# 7seg_clock_ver2.net
KiCad netlist of a schematic drawn in EAGLE
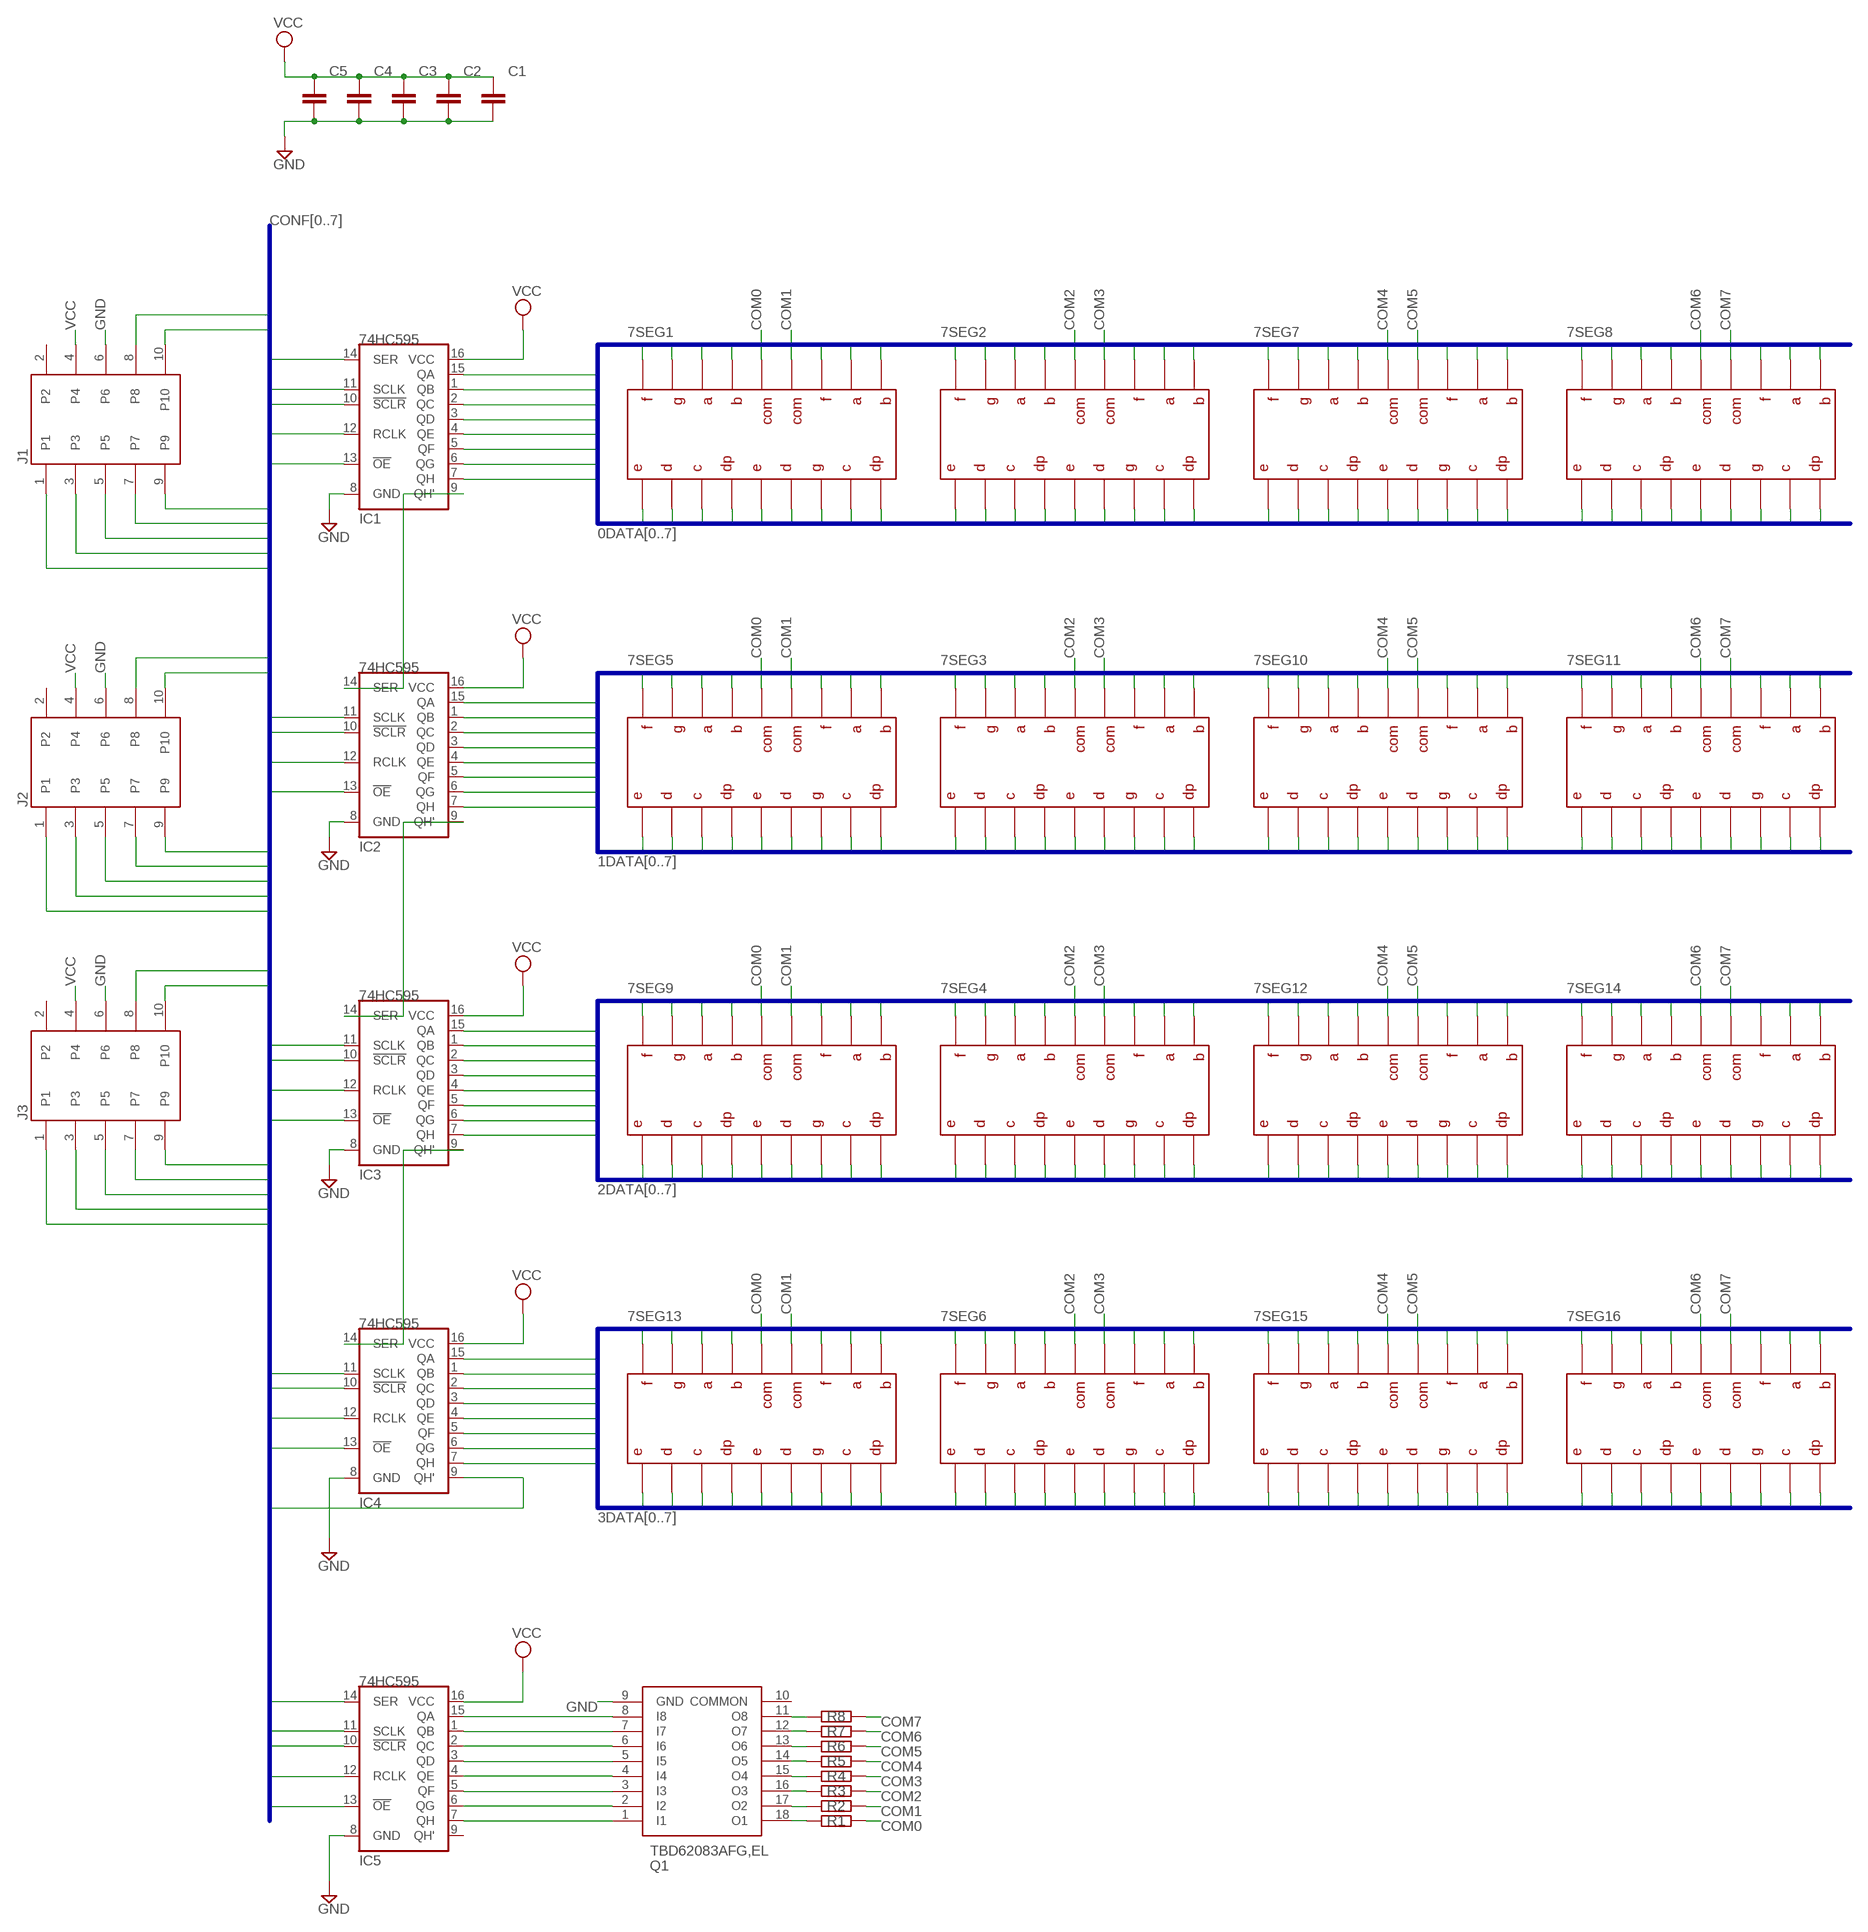
[diagram p0: schematic, sheet 1]

(export (version "E")
  (design (tool "Eeschema 10.0.6"))
  (components
    (comp (ref "7SEG1")
      (value "SL-3264")
      (footprint "eagle-import:SL-3264")
      (libsource (lib "eagle-import") (part "SL-3264"))
    )
    (comp (ref "7SEG2")
      (value "SL-3264")
      (footprint "eagle-import:SL-3264")
      (libsource (lib "eagle-import") (part "SL-3264"))
    )
    (comp (ref "7SEG3")
      (value "SL-3264")
      (footprint "eagle-import:SL-3264")
      (libsource (lib "eagle-import") (part "SL-3264"))
    )
    (comp (ref "7SEG4")
      (value "SL-3264")
      (footprint "eagle-import:SL-3264")
      (libsource (lib "eagle-import") (part "SL-3264"))
    )
    (comp (ref "7SEG5")
      (value "SL-3264")
      (footprint "eagle-import:SL-3264")
      (libsource (lib "eagle-import") (part "SL-3264"))
    )
    (comp (ref "7SEG6")
      (value "SL-3264")
      (footprint "eagle-import:SL-3264")
      (libsource (lib "eagle-import") (part "SL-3264"))
    )
    (comp (ref "7SEG7")
      (value "SL-3264")
      (footprint "eagle-import:SL-3264")
      (libsource (lib "eagle-import") (part "SL-3264"))
    )
    (comp (ref "7SEG8")
      (value "SL-3264")
      (footprint "eagle-import:SL-3264")
      (libsource (lib "eagle-import") (part "SL-3264"))
    )
    (comp (ref "7SEG9")
      (value "SL-3264")
      (footprint "eagle-import:SL-3264")
      (libsource (lib "eagle-import") (part "SL-3264"))
    )
    (comp (ref "7SEG10")
      (value "SL-3264")
      (footprint "eagle-import:SL-3264")
      (libsource (lib "eagle-import") (part "SL-3264"))
    )
    (comp (ref "7SEG11")
      (value "SL-3264")
      (footprint "eagle-import:SL-3264")
      (libsource (lib "eagle-import") (part "SL-3264"))
    )
    (comp (ref "7SEG12")
      (value "SL-3264")
      (footprint "eagle-import:SL-3264")
      (libsource (lib "eagle-import") (part "SL-3264"))
    )
    (comp (ref "7SEG13")
      (value "SL-3264")
      (footprint "eagle-import:SL-3264")
      (libsource (lib "eagle-import") (part "SL-3264"))
    )
    (comp (ref "7SEG14")
      (value "SL-3264")
      (footprint "eagle-import:SL-3264")
      (libsource (lib "eagle-import") (part "SL-3264"))
    )
    (comp (ref "7SEG15")
      (value "SL-3264")
      (footprint "eagle-import:SL-3264")
      (libsource (lib "eagle-import") (part "SL-3264"))
    )
    (comp (ref "7SEG16")
      (value "SL-3264")
      (footprint "eagle-import:SL-3264")
      (libsource (lib "eagle-import") (part "SL-3264"))
    )
    (comp (ref "C1")
      (value "C_CHIP-0603(1608-METRIC)")
      (footprint "eagle-import:CAPC1608X85")
      (libsource (lib "eagle-import") (part "CCHIP-0603(1608-METRIC)_"))
    )
    (comp (ref "C2")
      (value "C_CHIP-0603(1608-METRIC)")
      (footprint "eagle-import:CAPC1608X85")
      (libsource (lib "eagle-import") (part "CCHIP-0603(1608-METRIC)_"))
    )
    (comp (ref "C3")
      (value "C_CHIP-0603(1608-METRIC)")
      (footprint "eagle-import:CAPC1608X85")
      (libsource (lib "eagle-import") (part "CCHIP-0603(1608-METRIC)_"))
    )
    (comp (ref "C4")
      (value "C_CHIP-0603(1608-METRIC)")
      (footprint "eagle-import:CAPC1608X85")
      (libsource (lib "eagle-import") (part "CCHIP-0603(1608-METRIC)_"))
    )
    (comp (ref "C5")
      (value "C_CHIP-0603(1608-METRIC)")
      (footprint "eagle-import:CAPC1608X85")
      (libsource (lib "eagle-import") (part "CCHIP-0603(1608-METRIC)_"))
    )
    (comp (ref "IC1")
      (value "74HC595")
      (footprint "eagle-import:SO16")
      (fields (field (name "MF") "Nexperia"))
      (libsource (lib "eagle-import") (part "74HC595"))
    )
    (comp (ref "IC2")
      (value "74HC595")
      (footprint "eagle-import:SO16")
      (fields (field (name "MF") "Nexperia"))
      (libsource (lib "eagle-import") (part "74HC595"))
    )
    (comp (ref "IC3")
      (value "74HC595")
      (footprint "eagle-import:SO16")
      (fields (field (name "MF") "Nexperia"))
      (libsource (lib "eagle-import") (part "74HC595"))
    )
    (comp (ref "IC4")
      (value "74HC595")
      (footprint "eagle-import:SO16")
      (fields (field (name "MF") "Nexperia"))
      (libsource (lib "eagle-import") (part "74HC595"))
    )
    (comp (ref "IC5")
      (value "74HC595")
      (footprint "eagle-import:SO16")
      (fields (field (name "MF") "Nexperia"))
      (libsource (lib "eagle-import") (part "74HC595"))
    )
    (comp (ref "J1")
      (value "1241050-5")
      (footprint "eagle-import:TE_1241050-5")
      (fields (field (name "MF") "TE Connectivity"))
      (libsource (lib "eagle-import") (part "1241050-5"))
    )
    (comp (ref "J2")
      (value "1241050-5")
      (footprint "eagle-import:TE_1241050-5")
      (fields (field (name "MF") "TE Connectivity"))
      (libsource (lib "eagle-import") (part "1241050-5"))
    )
    (comp (ref "J3")
      (value "1241050-5")
      (footprint "eagle-import:TE_1241050-5")
      (fields (field (name "MF") "TE Connectivity"))
      (libsource (lib "eagle-import") (part "1241050-5"))
    )
    (comp (ref "Q1")
      (value "TBD62083AFG,EL")
      (footprint "eagle-import:SOIC127P1030X245-18N")
      (fields (field (name "MF") "Toshiba Semiconductor"))
      (libsource (lib "eagle-import") (part "TBD62083AFG,EL"))
    )
    (comp (ref "R1")
      (value "R_CHIP-0603(1608-METRIC)")
      (footprint "eagle-import:RESC1608X60")
      (libsource (lib "eagle-import") (part "RCHIP-0603(1608-METRIC)_"))
    )
    (comp (ref "R2")
      (value "R_CHIP-0603(1608-METRIC)")
      (footprint "eagle-import:RESC1608X60")
      (libsource (lib "eagle-import") (part "RCHIP-0603(1608-METRIC)_"))
    )
    (comp (ref "R3")
      (value "R_CHIP-0603(1608-METRIC)")
      (footprint "eagle-import:RESC1608X60")
      (libsource (lib "eagle-import") (part "RCHIP-0603(1608-METRIC)_"))
    )
    (comp (ref "R4")
      (value "R_CHIP-0603(1608-METRIC)")
      (footprint "eagle-import:RESC1608X60")
      (libsource (lib "eagle-import") (part "RCHIP-0603(1608-METRIC)_"))
    )
    (comp (ref "R5")
      (value "R_CHIP-0603(1608-METRIC)")
      (footprint "eagle-import:RESC1608X60")
      (libsource (lib "eagle-import") (part "RCHIP-0603(1608-METRIC)_"))
    )
    (comp (ref "R6")
      (value "R_CHIP-0603(1608-METRIC)")
      (footprint "eagle-import:RESC1608X60")
      (libsource (lib "eagle-import") (part "RCHIP-0603(1608-METRIC)_"))
    )
    (comp (ref "R7")
      (value "R_CHIP-0603(1608-METRIC)")
      (footprint "eagle-import:RESC1608X60")
      (libsource (lib "eagle-import") (part "RCHIP-0603(1608-METRIC)_"))
    )
    (comp (ref "R8")
      (value "R_CHIP-0603(1608-METRIC)")
      (footprint "eagle-import:RESC1608X60")
      (libsource (lib "eagle-import") (part "RCHIP-0603(1608-METRIC)_"))
    )
  )
  (nets
    (net (code "2") (name "/0DATA0") (class "Default")
      (node (ref "7SEG1") (pin "P$10") (pinfunction "P$10_P$10") (pintype "bidirectional"))
      (node (ref "7SEG1") (pin "P$15") (pinfunction "P$15_P$15") (pintype "bidirectional"))
      (node (ref "7SEG2") (pin "P$10") (pinfunction "P$10_P$10") (pintype "bidirectional"))
      (node (ref "7SEG2") (pin "P$15") (pinfunction "P$15_P$15") (pintype "bidirectional"))
      (node (ref "7SEG7") (pin "P$10") (pinfunction "P$10_P$10") (pintype "bidirectional"))
      (node (ref "7SEG7") (pin "P$15") (pinfunction "P$15_P$15") (pintype "bidirectional"))
      (node (ref "7SEG8") (pin "P$10") (pinfunction "P$10_P$10") (pintype "bidirectional"))
      (node (ref "7SEG8") (pin "P$15") (pinfunction "P$15_P$15") (pintype "bidirectional"))
      (node (ref "IC1") (pin "15") (pinfunction "QA_15") (pintype "tri_state"))
    )
    (net (code "3") (name "/0DATA1") (class "Default")
      (node (ref "7SEG1") (pin "P$12") (pinfunction "P$12_P$12") (pintype "bidirectional"))
      (node (ref "7SEG1") (pin "P$18") (pinfunction "P$18_P$18") (pintype "bidirectional"))
      (node (ref "7SEG2") (pin "P$12") (pinfunction "P$12_P$12") (pintype "bidirectional"))
      (node (ref "7SEG2") (pin "P$18") (pinfunction "P$18_P$18") (pintype "bidirectional"))
      (node (ref "7SEG7") (pin "P$12") (pinfunction "P$12_P$12") (pintype "bidirectional"))
      (node (ref "7SEG7") (pin "P$18") (pinfunction "P$18_P$18") (pintype "bidirectional"))
      (node (ref "7SEG8") (pin "P$12") (pinfunction "P$12_P$12") (pintype "bidirectional"))
      (node (ref "7SEG8") (pin "P$18") (pinfunction "P$18_P$18") (pintype "bidirectional"))
      (node (ref "IC1") (pin "1") (pinfunction "QB_1") (pintype "tri_state"))
    )
    (net (code "4") (name "/0DATA2") (class "Default")
      (node (ref "7SEG1") (pin "P$17") (pinfunction "P$17_P$17") (pintype "bidirectional"))
      (node (ref "7SEG1") (pin "P$7") (pinfunction "P$7_P$7") (pintype "bidirectional"))
      (node (ref "7SEG2") (pin "P$17") (pinfunction "P$17_P$17") (pintype "bidirectional"))
      (node (ref "7SEG2") (pin "P$7") (pinfunction "P$7_P$7") (pintype "bidirectional"))
      (node (ref "7SEG7") (pin "P$17") (pinfunction "P$17_P$17") (pintype "bidirectional"))
      (node (ref "7SEG7") (pin "P$7") (pinfunction "P$7_P$7") (pintype "bidirectional"))
      (node (ref "7SEG8") (pin "P$17") (pinfunction "P$17_P$17") (pintype "bidirectional"))
      (node (ref "7SEG8") (pin "P$7") (pinfunction "P$7_P$7") (pintype "bidirectional"))
      (node (ref "IC1") (pin "2") (pinfunction "QC_2") (pintype "tri_state"))
    )
    (net (code "5") (name "/0DATA3") (class "Default")
      (node (ref "7SEG1") (pin "P$11") (pinfunction "P$11_P$11") (pintype "bidirectional"))
      (node (ref "7SEG1") (pin "P$16") (pinfunction "P$16_P$16") (pintype "bidirectional"))
      (node (ref "7SEG2") (pin "P$11") (pinfunction "P$11_P$11") (pintype "bidirectional"))
      (node (ref "7SEG2") (pin "P$16") (pinfunction "P$16_P$16") (pintype "bidirectional"))
      (node (ref "7SEG7") (pin "P$11") (pinfunction "P$11_P$11") (pintype "bidirectional"))
      (node (ref "7SEG7") (pin "P$16") (pinfunction "P$16_P$16") (pintype "bidirectional"))
      (node (ref "7SEG8") (pin "P$11") (pinfunction "P$11_P$11") (pintype "bidirectional"))
      (node (ref "7SEG8") (pin "P$16") (pinfunction "P$16_P$16") (pintype "bidirectional"))
      (node (ref "IC1") (pin "3") (pinfunction "QD_3") (pintype "tri_state"))
    )
    (net (code "6") (name "/0DATA4") (class "Default")
      (node (ref "7SEG1") (pin "P$4") (pinfunction "P$4_P$4") (pintype "bidirectional"))
      (node (ref "7SEG1") (pin "P$9") (pinfunction "P$9_P$9") (pintype "bidirectional"))
      (node (ref "7SEG2") (pin "P$4") (pinfunction "P$4_P$4") (pintype "bidirectional"))
      (node (ref "7SEG2") (pin "P$9") (pinfunction "P$9_P$9") (pintype "bidirectional"))
      (node (ref "7SEG7") (pin "P$4") (pinfunction "P$4_P$4") (pintype "bidirectional"))
      (node (ref "7SEG7") (pin "P$9") (pinfunction "P$9_P$9") (pintype "bidirectional"))
      (node (ref "7SEG8") (pin "P$4") (pinfunction "P$4_P$4") (pintype "bidirectional"))
      (node (ref "7SEG8") (pin "P$9") (pinfunction "P$9_P$9") (pintype "bidirectional"))
      (node (ref "IC1") (pin "4") (pinfunction "QE_4") (pintype "tri_state"))
    )
    (net (code "7") (name "/0DATA5") (class "Default")
      (node (ref "7SEG1") (pin "P$3") (pinfunction "P$3_P$3") (pintype "bidirectional"))
      (node (ref "7SEG1") (pin "P$8") (pinfunction "P$8_P$8") (pintype "bidirectional"))
      (node (ref "7SEG2") (pin "P$3") (pinfunction "P$3_P$3") (pintype "bidirectional"))
      (node (ref "7SEG2") (pin "P$8") (pinfunction "P$8_P$8") (pintype "bidirectional"))
      (node (ref "7SEG7") (pin "P$3") (pinfunction "P$3_P$3") (pintype "bidirectional"))
      (node (ref "7SEG7") (pin "P$8") (pinfunction "P$8_P$8") (pintype "bidirectional"))
      (node (ref "7SEG8") (pin "P$3") (pinfunction "P$3_P$3") (pintype "bidirectional"))
      (node (ref "7SEG8") (pin "P$8") (pinfunction "P$8_P$8") (pintype "bidirectional"))
      (node (ref "IC1") (pin "5") (pinfunction "QF_5") (pintype "tri_state"))
    )
    (net (code "8") (name "/0DATA6") (class "Default")
      (node (ref "7SEG1") (pin "P$2") (pinfunction "P$2_P$2") (pintype "bidirectional"))
      (node (ref "7SEG1") (pin "P$6") (pinfunction "P$6_P$6") (pintype "bidirectional"))
      (node (ref "7SEG2") (pin "P$2") (pinfunction "P$2_P$2") (pintype "bidirectional"))
      (node (ref "7SEG2") (pin "P$6") (pinfunction "P$6_P$6") (pintype "bidirectional"))
      (node (ref "7SEG7") (pin "P$2") (pinfunction "P$2_P$2") (pintype "bidirectional"))
      (node (ref "7SEG7") (pin "P$6") (pinfunction "P$6_P$6") (pintype "bidirectional"))
      (node (ref "7SEG8") (pin "P$2") (pinfunction "P$2_P$2") (pintype "bidirectional"))
      (node (ref "7SEG8") (pin "P$6") (pinfunction "P$6_P$6") (pintype "bidirectional"))
      (node (ref "IC1") (pin "6") (pinfunction "QG_6") (pintype "tri_state"))
    )
    (net (code "9") (name "/0DATA7") (class "Default")
      (node (ref "7SEG1") (pin "P$1") (pinfunction "P$1_P$1") (pintype "bidirectional"))
      (node (ref "7SEG1") (pin "P$5") (pinfunction "P$5_P$5") (pintype "bidirectional"))
      (node (ref "7SEG2") (pin "P$1") (pinfunction "P$1_P$1") (pintype "bidirectional"))
      (node (ref "7SEG2") (pin "P$5") (pinfunction "P$5_P$5") (pintype "bidirectional"))
      (node (ref "7SEG7") (pin "P$1") (pinfunction "P$1_P$1") (pintype "bidirectional"))
      (node (ref "7SEG7") (pin "P$5") (pinfunction "P$5_P$5") (pintype "bidirectional"))
      (node (ref "7SEG8") (pin "P$1") (pinfunction "P$1_P$1") (pintype "bidirectional"))
      (node (ref "7SEG8") (pin "P$5") (pinfunction "P$5_P$5") (pintype "bidirectional"))
      (node (ref "IC1") (pin "7") (pinfunction "QH_7") (pintype "tri_state"))
    )
    (net (code "11") (name "/1DATA0") (class "Default")
      (node (ref "7SEG10") (pin "P$10") (pinfunction "P$10_P$10") (pintype "bidirectional"))
      (node (ref "7SEG10") (pin "P$15") (pinfunction "P$15_P$15") (pintype "bidirectional"))
      (node (ref "7SEG11") (pin "P$10") (pinfunction "P$10_P$10") (pintype "bidirectional"))
      (node (ref "7SEG11") (pin "P$15") (pinfunction "P$15_P$15") (pintype "bidirectional"))
      (node (ref "7SEG3") (pin "P$10") (pinfunction "P$10_P$10") (pintype "bidirectional"))
      (node (ref "7SEG3") (pin "P$15") (pinfunction "P$15_P$15") (pintype "bidirectional"))
      (node (ref "7SEG5") (pin "P$10") (pinfunction "P$10_P$10") (pintype "bidirectional"))
      (node (ref "7SEG5") (pin "P$15") (pinfunction "P$15_P$15") (pintype "bidirectional"))
      (node (ref "IC2") (pin "15") (pinfunction "QA_15") (pintype "tri_state"))
    )
    (net (code "12") (name "/1DATA1") (class "Default")
      (node (ref "7SEG10") (pin "P$12") (pinfunction "P$12_P$12") (pintype "bidirectional"))
      (node (ref "7SEG10") (pin "P$18") (pinfunction "P$18_P$18") (pintype "bidirectional"))
      (node (ref "7SEG11") (pin "P$12") (pinfunction "P$12_P$12") (pintype "bidirectional"))
      (node (ref "7SEG11") (pin "P$18") (pinfunction "P$18_P$18") (pintype "bidirectional"))
      (node (ref "7SEG3") (pin "P$12") (pinfunction "P$12_P$12") (pintype "bidirectional"))
      (node (ref "7SEG3") (pin "P$18") (pinfunction "P$18_P$18") (pintype "bidirectional"))
      (node (ref "7SEG5") (pin "P$12") (pinfunction "P$12_P$12") (pintype "bidirectional"))
      (node (ref "7SEG5") (pin "P$18") (pinfunction "P$18_P$18") (pintype "bidirectional"))
      (node (ref "IC2") (pin "1") (pinfunction "QB_1") (pintype "tri_state"))
    )
    (net (code "13") (name "/1DATA2") (class "Default")
      (node (ref "7SEG10") (pin "P$17") (pinfunction "P$17_P$17") (pintype "bidirectional"))
      (node (ref "7SEG10") (pin "P$7") (pinfunction "P$7_P$7") (pintype "bidirectional"))
      (node (ref "7SEG11") (pin "P$17") (pinfunction "P$17_P$17") (pintype "bidirectional"))
      (node (ref "7SEG11") (pin "P$7") (pinfunction "P$7_P$7") (pintype "bidirectional"))
      (node (ref "7SEG3") (pin "P$17") (pinfunction "P$17_P$17") (pintype "bidirectional"))
      (node (ref "7SEG3") (pin "P$7") (pinfunction "P$7_P$7") (pintype "bidirectional"))
      (node (ref "7SEG5") (pin "P$17") (pinfunction "P$17_P$17") (pintype "bidirectional"))
      (node (ref "7SEG5") (pin "P$7") (pinfunction "P$7_P$7") (pintype "bidirectional"))
      (node (ref "IC2") (pin "2") (pinfunction "QC_2") (pintype "tri_state"))
    )
    (net (code "14") (name "/1DATA3") (class "Default")
      (node (ref "7SEG10") (pin "P$11") (pinfunction "P$11_P$11") (pintype "bidirectional"))
      (node (ref "7SEG10") (pin "P$16") (pinfunction "P$16_P$16") (pintype "bidirectional"))
      (node (ref "7SEG11") (pin "P$11") (pinfunction "P$11_P$11") (pintype "bidirectional"))
      (node (ref "7SEG11") (pin "P$16") (pinfunction "P$16_P$16") (pintype "bidirectional"))
      (node (ref "7SEG3") (pin "P$11") (pinfunction "P$11_P$11") (pintype "bidirectional"))
      (node (ref "7SEG3") (pin "P$16") (pinfunction "P$16_P$16") (pintype "bidirectional"))
      (node (ref "7SEG5") (pin "P$11") (pinfunction "P$11_P$11") (pintype "bidirectional"))
      (node (ref "7SEG5") (pin "P$16") (pinfunction "P$16_P$16") (pintype "bidirectional"))
      (node (ref "IC2") (pin "3") (pinfunction "QD_3") (pintype "tri_state"))
    )
    (net (code "15") (name "/1DATA4") (class "Default")
      (node (ref "7SEG10") (pin "P$4") (pinfunction "P$4_P$4") (pintype "bidirectional"))
      (node (ref "7SEG10") (pin "P$9") (pinfunction "P$9_P$9") (pintype "bidirectional"))
      (node (ref "7SEG11") (pin "P$4") (pinfunction "P$4_P$4") (pintype "bidirectional"))
      (node (ref "7SEG11") (pin "P$9") (pinfunction "P$9_P$9") (pintype "bidirectional"))
      (node (ref "7SEG3") (pin "P$4") (pinfunction "P$4_P$4") (pintype "bidirectional"))
      (node (ref "7SEG3") (pin "P$9") (pinfunction "P$9_P$9") (pintype "bidirectional"))
      (node (ref "7SEG5") (pin "P$4") (pinfunction "P$4_P$4") (pintype "bidirectional"))
      (node (ref "7SEG5") (pin "P$9") (pinfunction "P$9_P$9") (pintype "bidirectional"))
      (node (ref "IC2") (pin "4") (pinfunction "QE_4") (pintype "tri_state"))
    )
    (net (code "16") (name "/1DATA5") (class "Default")
      (node (ref "7SEG10") (pin "P$3") (pinfunction "P$3_P$3") (pintype "bidirectional"))
      (node (ref "7SEG10") (pin "P$8") (pinfunction "P$8_P$8") (pintype "bidirectional"))
      (node (ref "7SEG11") (pin "P$3") (pinfunction "P$3_P$3") (pintype "bidirectional"))
      (node (ref "7SEG11") (pin "P$8") (pinfunction "P$8_P$8") (pintype "bidirectional"))
      (node (ref "7SEG3") (pin "P$3") (pinfunction "P$3_P$3") (pintype "bidirectional"))
      (node (ref "7SEG3") (pin "P$8") (pinfunction "P$8_P$8") (pintype "bidirectional"))
      (node (ref "7SEG5") (pin "P$3") (pinfunction "P$3_P$3") (pintype "bidirectional"))
      (node (ref "7SEG5") (pin "P$8") (pinfunction "P$8_P$8") (pintype "bidirectional"))
      (node (ref "IC2") (pin "5") (pinfunction "QF_5") (pintype "tri_state"))
    )
    (net (code "17") (name "/1DATA6") (class "Default")
      (node (ref "7SEG10") (pin "P$2") (pinfunction "P$2_P$2") (pintype "bidirectional"))
      (node (ref "7SEG10") (pin "P$6") (pinfunction "P$6_P$6") (pintype "bidirectional"))
      (node (ref "7SEG11") (pin "P$2") (pinfunction "P$2_P$2") (pintype "bidirectional"))
      (node (ref "7SEG11") (pin "P$6") (pinfunction "P$6_P$6") (pintype "bidirectional"))
      (node (ref "7SEG3") (pin "P$2") (pinfunction "P$2_P$2") (pintype "bidirectional"))
      (node (ref "7SEG3") (pin "P$6") (pinfunction "P$6_P$6") (pintype "bidirectional"))
      (node (ref "7SEG5") (pin "P$2") (pinfunction "P$2_P$2") (pintype "bidirectional"))
      (node (ref "7SEG5") (pin "P$6") (pinfunction "P$6_P$6") (pintype "bidirectional"))
      (node (ref "IC2") (pin "6") (pinfunction "QG_6") (pintype "tri_state"))
    )
    (net (code "18") (name "/1DATA7") (class "Default")
      (node (ref "7SEG10") (pin "P$1") (pinfunction "P$1_P$1") (pintype "bidirectional"))
      (node (ref "7SEG10") (pin "P$5") (pinfunction "P$5_P$5") (pintype "bidirectional"))
      (node (ref "7SEG11") (pin "P$1") (pinfunction "P$1_P$1") (pintype "bidirectional"))
      (node (ref "7SEG11") (pin "P$5") (pinfunction "P$5_P$5") (pintype "bidirectional"))
      (node (ref "7SEG3") (pin "P$1") (pinfunction "P$1_P$1") (pintype "bidirectional"))
      (node (ref "7SEG3") (pin "P$5") (pinfunction "P$5_P$5") (pintype "bidirectional"))
      (node (ref "7SEG5") (pin "P$1") (pinfunction "P$1_P$1") (pintype "bidirectional"))
      (node (ref "7SEG5") (pin "P$5") (pinfunction "P$5_P$5") (pintype "bidirectional"))
      (node (ref "IC2") (pin "7") (pinfunction "QH_7") (pintype "tri_state"))
    )
    (net (code "20") (name "/2DATA0") (class "Default")
      (node (ref "7SEG12") (pin "P$10") (pinfunction "P$10_P$10") (pintype "bidirectional"))
      (node (ref "7SEG12") (pin "P$15") (pinfunction "P$15_P$15") (pintype "bidirectional"))
      (node (ref "7SEG14") (pin "P$10") (pinfunction "P$10_P$10") (pintype "bidirectional"))
      (node (ref "7SEG14") (pin "P$15") (pinfunction "P$15_P$15") (pintype "bidirectional"))
      (node (ref "7SEG4") (pin "P$10") (pinfunction "P$10_P$10") (pintype "bidirectional"))
      (node (ref "7SEG4") (pin "P$15") (pinfunction "P$15_P$15") (pintype "bidirectional"))
      (node (ref "7SEG9") (pin "P$10") (pinfunction "P$10_P$10") (pintype "bidirectional"))
      (node (ref "7SEG9") (pin "P$15") (pinfunction "P$15_P$15") (pintype "bidirectional"))
      (node (ref "IC3") (pin "15") (pinfunction "QA_15") (pintype "tri_state"))
    )
    (net (code "21") (name "/2DATA1") (class "Default")
      (node (ref "7SEG12") (pin "P$12") (pinfunction "P$12_P$12") (pintype "bidirectional"))
      (node (ref "7SEG12") (pin "P$18") (pinfunction "P$18_P$18") (pintype "bidirectional"))
      (node (ref "7SEG14") (pin "P$12") (pinfunction "P$12_P$12") (pintype "bidirectional"))
      (node (ref "7SEG14") (pin "P$18") (pinfunction "P$18_P$18") (pintype "bidirectional"))
      (node (ref "7SEG4") (pin "P$12") (pinfunction "P$12_P$12") (pintype "bidirectional"))
      (node (ref "7SEG4") (pin "P$18") (pinfunction "P$18_P$18") (pintype "bidirectional"))
      (node (ref "7SEG9") (pin "P$12") (pinfunction "P$12_P$12") (pintype "bidirectional"))
      (node (ref "7SEG9") (pin "P$18") (pinfunction "P$18_P$18") (pintype "bidirectional"))
      (node (ref "IC3") (pin "1") (pinfunction "QB_1") (pintype "tri_state"))
    )
    (net (code "22") (name "/2DATA2") (class "Default")
      (node (ref "7SEG12") (pin "P$17") (pinfunction "P$17_P$17") (pintype "bidirectional"))
      (node (ref "7SEG12") (pin "P$7") (pinfunction "P$7_P$7") (pintype "bidirectional"))
      (node (ref "7SEG14") (pin "P$17") (pinfunction "P$17_P$17") (pintype "bidirectional"))
      (node (ref "7SEG14") (pin "P$7") (pinfunction "P$7_P$7") (pintype "bidirectional"))
      (node (ref "7SEG4") (pin "P$17") (pinfunction "P$17_P$17") (pintype "bidirectional"))
      (node (ref "7SEG4") (pin "P$7") (pinfunction "P$7_P$7") (pintype "bidirectional"))
      (node (ref "7SEG9") (pin "P$17") (pinfunction "P$17_P$17") (pintype "bidirectional"))
      (node (ref "7SEG9") (pin "P$7") (pinfunction "P$7_P$7") (pintype "bidirectional"))
      (node (ref "IC3") (pin "2") (pinfunction "QC_2") (pintype "tri_state"))
    )
    (net (code "23") (name "/2DATA3") (class "Default")
      (node (ref "7SEG12") (pin "P$11") (pinfunction "P$11_P$11") (pintype "bidirectional"))
      (node (ref "7SEG12") (pin "P$16") (pinfunction "P$16_P$16") (pintype "bidirectional"))
      (node (ref "7SEG14") (pin "P$11") (pinfunction "P$11_P$11") (pintype "bidirectional"))
      (node (ref "7SEG14") (pin "P$16") (pinfunction "P$16_P$16") (pintype "bidirectional"))
      (node (ref "7SEG4") (pin "P$11") (pinfunction "P$11_P$11") (pintype "bidirectional"))
      (node (ref "7SEG4") (pin "P$16") (pinfunction "P$16_P$16") (pintype "bidirectional"))
      (node (ref "7SEG9") (pin "P$11") (pinfunction "P$11_P$11") (pintype "bidirectional"))
      (node (ref "7SEG9") (pin "P$16") (pinfunction "P$16_P$16") (pintype "bidirectional"))
      (node (ref "IC3") (pin "3") (pinfunction "QD_3") (pintype "tri_state"))
    )
    (net (code "24") (name "/2DATA4") (class "Default")
      (node (ref "7SEG12") (pin "P$4") (pinfunction "P$4_P$4") (pintype "bidirectional"))
      (node (ref "7SEG12") (pin "P$9") (pinfunction "P$9_P$9") (pintype "bidirectional"))
      (node (ref "7SEG14") (pin "P$4") (pinfunction "P$4_P$4") (pintype "bidirectional"))
      (node (ref "7SEG14") (pin "P$9") (pinfunction "P$9_P$9") (pintype "bidirectional"))
      (node (ref "7SEG4") (pin "P$4") (pinfunction "P$4_P$4") (pintype "bidirectional"))
      (node (ref "7SEG4") (pin "P$9") (pinfunction "P$9_P$9") (pintype "bidirectional"))
      (node (ref "7SEG9") (pin "P$4") (pinfunction "P$4_P$4") (pintype "bidirectional"))
      (node (ref "7SEG9") (pin "P$9") (pinfunction "P$9_P$9") (pintype "bidirectional"))
      (node (ref "IC3") (pin "4") (pinfunction "QE_4") (pintype "tri_state"))
    )
    (net (code "25") (name "/2DATA5") (class "Default")
      (node (ref "7SEG12") (pin "P$3") (pinfunction "P$3_P$3") (pintype "bidirectional"))
      (node (ref "7SEG12") (pin "P$8") (pinfunction "P$8_P$8") (pintype "bidirectional"))
      (node (ref "7SEG14") (pin "P$3") (pinfunction "P$3_P$3") (pintype "bidirectional"))
      (node (ref "7SEG14") (pin "P$8") (pinfunction "P$8_P$8") (pintype "bidirectional"))
      (node (ref "7SEG4") (pin "P$3") (pinfunction "P$3_P$3") (pintype "bidirectional"))
      (node (ref "7SEG4") (pin "P$8") (pinfunction "P$8_P$8") (pintype "bidirectional"))
      (node (ref "7SEG9") (pin "P$3") (pinfunction "P$3_P$3") (pintype "bidirectional"))
      (node (ref "7SEG9") (pin "P$8") (pinfunction "P$8_P$8") (pintype "bidirectional"))
      (node (ref "IC3") (pin "5") (pinfunction "QF_5") (pintype "tri_state"))
    )
    (net (code "26") (name "/2DATA6") (class "Default")
      (node (ref "7SEG12") (pin "P$2") (pinfunction "P$2_P$2") (pintype "bidirectional"))
      (node (ref "7SEG12") (pin "P$6") (pinfunction "P$6_P$6") (pintype "bidirectional"))
      (node (ref "7SEG14") (pin "P$2") (pinfunction "P$2_P$2") (pintype "bidirectional"))
      (node (ref "7SEG14") (pin "P$6") (pinfunction "P$6_P$6") (pintype "bidirectional"))
      (node (ref "7SEG4") (pin "P$2") (pinfunction "P$2_P$2") (pintype "bidirectional"))
      (node (ref "7SEG4") (pin "P$6") (pinfunction "P$6_P$6") (pintype "bidirectional"))
      (node (ref "7SEG9") (pin "P$2") (pinfunction "P$2_P$2") (pintype "bidirectional"))
      (node (ref "7SEG9") (pin "P$6") (pinfunction "P$6_P$6") (pintype "bidirectional"))
      (node (ref "IC3") (pin "6") (pinfunction "QG_6") (pintype "tri_state"))
    )
    (net (code "27") (name "/2DATA7") (class "Default")
      (node (ref "7SEG12") (pin "P$1") (pinfunction "P$1_P$1") (pintype "bidirectional"))
      (node (ref "7SEG12") (pin "P$5") (pinfunction "P$5_P$5") (pintype "bidirectional"))
      (node (ref "7SEG14") (pin "P$1") (pinfunction "P$1_P$1") (pintype "bidirectional"))
      (node (ref "7SEG14") (pin "P$5") (pinfunction "P$5_P$5") (pintype "bidirectional"))
      (node (ref "7SEG4") (pin "P$1") (pinfunction "P$1_P$1") (pintype "bidirectional"))
      (node (ref "7SEG4") (pin "P$5") (pinfunction "P$5_P$5") (pintype "bidirectional"))
      (node (ref "7SEG9") (pin "P$1") (pinfunction "P$1_P$1") (pintype "bidirectional"))
      (node (ref "7SEG9") (pin "P$5") (pinfunction "P$5_P$5") (pintype "bidirectional"))
      (node (ref "IC3") (pin "7") (pinfunction "QH_7") (pintype "tri_state"))
    )
    (net (code "29") (name "/3DATA0") (class "Default")
      (node (ref "7SEG13") (pin "P$10") (pinfunction "P$10_P$10") (pintype "bidirectional"))
      (node (ref "7SEG13") (pin "P$15") (pinfunction "P$15_P$15") (pintype "bidirectional"))
      (node (ref "7SEG15") (pin "P$10") (pinfunction "P$10_P$10") (pintype "bidirectional"))
      (node (ref "7SEG15") (pin "P$15") (pinfunction "P$15_P$15") (pintype "bidirectional"))
      (node (ref "7SEG16") (pin "P$10") (pinfunction "P$10_P$10") (pintype "bidirectional"))
      (node (ref "7SEG16") (pin "P$15") (pinfunction "P$15_P$15") (pintype "bidirectional"))
      (node (ref "7SEG6") (pin "P$10") (pinfunction "P$10_P$10") (pintype "bidirectional"))
      (node (ref "7SEG6") (pin "P$15") (pinfunction "P$15_P$15") (pintype "bidirectional"))
      (node (ref "IC4") (pin "15") (pinfunction "QA_15") (pintype "tri_state"))
    )
    (net (code "30") (name "/3DATA1") (class "Default")
      (node (ref "7SEG13") (pin "P$12") (pinfunction "P$12_P$12") (pintype "bidirectional"))
      (node (ref "7SEG13") (pin "P$18") (pinfunction "P$18_P$18") (pintype "bidirectional"))
      (node (ref "7SEG15") (pin "P$12") (pinfunction "P$12_P$12") (pintype "bidirectional"))
      (node (ref "7SEG15") (pin "P$18") (pinfunction "P$18_P$18") (pintype "bidirectional"))
      (node (ref "7SEG16") (pin "P$12") (pinfunction "P$12_P$12") (pintype "bidirectional"))
      (node (ref "7SEG16") (pin "P$18") (pinfunction "P$18_P$18") (pintype "bidirectional"))
      (node (ref "7SEG6") (pin "P$12") (pinfunction "P$12_P$12") (pintype "bidirectional"))
      (node (ref "7SEG6") (pin "P$18") (pinfunction "P$18_P$18") (pintype "bidirectional"))
      (node (ref "IC4") (pin "1") (pinfunction "QB_1") (pintype "tri_state"))
    )
    (net (code "31") (name "/3DATA2") (class "Default")
      (node (ref "7SEG13") (pin "P$17") (pinfunction "P$17_P$17") (pintype "bidirectional"))
      (node (ref "7SEG13") (pin "P$7") (pinfunction "P$7_P$7") (pintype "bidirectional"))
      (node (ref "7SEG15") (pin "P$17") (pinfunction "P$17_P$17") (pintype "bidirectional"))
      (node (ref "7SEG15") (pin "P$7") (pinfunction "P$7_P$7") (pintype "bidirectional"))
      (node (ref "7SEG16") (pin "P$17") (pinfunction "P$17_P$17") (pintype "bidirectional"))
      (node (ref "7SEG16") (pin "P$7") (pinfunction "P$7_P$7") (pintype "bidirectional"))
      (node (ref "7SEG6") (pin "P$17") (pinfunction "P$17_P$17") (pintype "bidirectional"))
      (node (ref "7SEG6") (pin "P$7") (pinfunction "P$7_P$7") (pintype "bidirectional"))
      (node (ref "IC4") (pin "2") (pinfunction "QC_2") (pintype "tri_state"))
    )
    (net (code "32") (name "/3DATA3") (class "Default")
      (node (ref "7SEG13") (pin "P$11") (pinfunction "P$11_P$11") (pintype "bidirectional"))
      (node (ref "7SEG13") (pin "P$16") (pinfunction "P$16_P$16") (pintype "bidirectional"))
      (node (ref "7SEG15") (pin "P$11") (pinfunction "P$11_P$11") (pintype "bidirectional"))
      (node (ref "7SEG15") (pin "P$16") (pinfunction "P$16_P$16") (pintype "bidirectional"))
      (node (ref "7SEG16") (pin "P$11") (pinfunction "P$11_P$11") (pintype "bidirectional"))
      (node (ref "7SEG16") (pin "P$16") (pinfunction "P$16_P$16") (pintype "bidirectional"))
      (node (ref "7SEG6") (pin "P$11") (pinfunction "P$11_P$11") (pintype "bidirectional"))
      (node (ref "7SEG6") (pin "P$16") (pinfunction "P$16_P$16") (pintype "bidirectional"))
      (node (ref "IC4") (pin "3") (pinfunction "QD_3") (pintype "tri_state"))
    )
    (net (code "33") (name "/3DATA4") (class "Default")
      (node (ref "7SEG13") (pin "P$4") (pinfunction "P$4_P$4") (pintype "bidirectional"))
      (node (ref "7SEG13") (pin "P$9") (pinfunction "P$9_P$9") (pintype "bidirectional"))
      (node (ref "7SEG15") (pin "P$4") (pinfunction "P$4_P$4") (pintype "bidirectional"))
      (node (ref "7SEG15") (pin "P$9") (pinfunction "P$9_P$9") (pintype "bidirectional"))
      (node (ref "7SEG16") (pin "P$4") (pinfunction "P$4_P$4") (pintype "bidirectional"))
      (node (ref "7SEG16") (pin "P$9") (pinfunction "P$9_P$9") (pintype "bidirectional"))
      (node (ref "7SEG6") (pin "P$4") (pinfunction "P$4_P$4") (pintype "bidirectional"))
      (node (ref "7SEG6") (pin "P$9") (pinfunction "P$9_P$9") (pintype "bidirectional"))
      (node (ref "IC4") (pin "4") (pinfunction "QE_4") (pintype "tri_state"))
    )
    (net (code "34") (name "/3DATA5") (class "Default")
      (node (ref "7SEG13") (pin "P$3") (pinfunction "P$3_P$3") (pintype "bidirectional"))
      (node (ref "7SEG13") (pin "P$8") (pinfunction "P$8_P$8") (pintype "bidirectional"))
      (node (ref "7SEG15") (pin "P$3") (pinfunction "P$3_P$3") (pintype "bidirectional"))
      (node (ref "7SEG15") (pin "P$8") (pinfunction "P$8_P$8") (pintype "bidirectional"))
      (node (ref "7SEG16") (pin "P$3") (pinfunction "P$3_P$3") (pintype "bidirectional"))
      (node (ref "7SEG16") (pin "P$8") (pinfunction "P$8_P$8") (pintype "bidirectional"))
      (node (ref "7SEG6") (pin "P$3") (pinfunction "P$3_P$3") (pintype "bidirectional"))
      (node (ref "7SEG6") (pin "P$8") (pinfunction "P$8_P$8") (pintype "bidirectional"))
      (node (ref "IC4") (pin "5") (pinfunction "QF_5") (pintype "tri_state"))
    )
    (net (code "35") (name "/3DATA6") (class "Default")
      (node (ref "7SEG13") (pin "P$2") (pinfunction "P$2_P$2") (pintype "bidirectional"))
      (node (ref "7SEG13") (pin "P$6") (pinfunction "P$6_P$6") (pintype "bidirectional"))
      (node (ref "7SEG15") (pin "P$2") (pinfunction "P$2_P$2") (pintype "bidirectional"))
      (node (ref "7SEG15") (pin "P$6") (pinfunction "P$6_P$6") (pintype "bidirectional"))
      (node (ref "7SEG16") (pin "P$2") (pinfunction "P$2_P$2") (pintype "bidirectional"))
      (node (ref "7SEG16") (pin "P$6") (pinfunction "P$6_P$6") (pintype "bidirectional"))
      (node (ref "7SEG6") (pin "P$2") (pinfunction "P$2_P$2") (pintype "bidirectional"))
      (node (ref "7SEG6") (pin "P$6") (pinfunction "P$6_P$6") (pintype "bidirectional"))
      (node (ref "IC4") (pin "6") (pinfunction "QG_6") (pintype "tri_state"))
    )
    (net (code "36") (name "/3DATA7") (class "Default")
      (node (ref "7SEG13") (pin "P$1") (pinfunction "P$1_P$1") (pintype "bidirectional"))
      (node (ref "7SEG13") (pin "P$5") (pinfunction "P$5_P$5") (pintype "bidirectional"))
      (node (ref "7SEG15") (pin "P$1") (pinfunction "P$1_P$1") (pintype "bidirectional"))
      (node (ref "7SEG15") (pin "P$5") (pinfunction "P$5_P$5") (pintype "bidirectional"))
      (node (ref "7SEG16") (pin "P$1") (pinfunction "P$1_P$1") (pintype "bidirectional"))
      (node (ref "7SEG16") (pin "P$5") (pinfunction "P$5_P$5") (pintype "bidirectional"))
      (node (ref "7SEG6") (pin "P$1") (pinfunction "P$1_P$1") (pintype "bidirectional"))
      (node (ref "7SEG6") (pin "P$5") (pinfunction "P$5_P$5") (pintype "bidirectional"))
      (node (ref "IC4") (pin "7") (pinfunction "QH_7") (pintype "tri_state"))
    )
    (net (code "38") (name "/COM0") (class "Default")
      (node (ref "7SEG1") (pin "P$14") (pinfunction "P$14_P$14") (pintype "power_in"))
      (node (ref "7SEG13") (pin "P$14") (pinfunction "P$14_P$14") (pintype "power_in"))
      (node (ref "7SEG5") (pin "P$14") (pinfunction "P$14_P$14") (pintype "power_in"))
      (node (ref "7SEG9") (pin "P$14") (pinfunction "P$14_P$14") (pintype "power_in"))
      (node (ref "R1") (pin "2") (pinfunction "2_2") (pintype "passive"))
    )
    (net (code "39") (name "/COM1") (class "Default")
      (node (ref "7SEG1") (pin "P$13") (pinfunction "P$13_P$13") (pintype "power_in"))
      (node (ref "7SEG13") (pin "P$13") (pinfunction "P$13_P$13") (pintype "power_in"))
      (node (ref "7SEG5") (pin "P$13") (pinfunction "P$13_P$13") (pintype "power_in"))
      (node (ref "7SEG9") (pin "P$13") (pinfunction "P$13_P$13") (pintype "power_in"))
      (node (ref "R2") (pin "2") (pinfunction "2_2") (pintype "passive"))
    )
    (net (code "40") (name "/COM2") (class "Default")
      (node (ref "7SEG2") (pin "P$14") (pinfunction "P$14_P$14") (pintype "power_in"))
      (node (ref "7SEG3") (pin "P$14") (pinfunction "P$14_P$14") (pintype "power_in"))
      (node (ref "7SEG4") (pin "P$14") (pinfunction "P$14_P$14") (pintype "power_in"))
      (node (ref "7SEG6") (pin "P$14") (pinfunction "P$14_P$14") (pintype "power_in"))
      (node (ref "R3") (pin "2") (pinfunction "2_2") (pintype "passive"))
    )
    (net (code "41") (name "/COM3") (class "Default")
      (node (ref "7SEG2") (pin "P$13") (pinfunction "P$13_P$13") (pintype "power_in"))
      (node (ref "7SEG3") (pin "P$13") (pinfunction "P$13_P$13") (pintype "power_in"))
      (node (ref "7SEG4") (pin "P$13") (pinfunction "P$13_P$13") (pintype "power_in"))
      (node (ref "7SEG6") (pin "P$13") (pinfunction "P$13_P$13") (pintype "power_in"))
      (node (ref "R4") (pin "2") (pinfunction "2_2") (pintype "passive"))
    )
    (net (code "42") (name "/COM4") (class "Default")
      (node (ref "7SEG10") (pin "P$14") (pinfunction "P$14_P$14") (pintype "power_in"))
      (node (ref "7SEG12") (pin "P$14") (pinfunction "P$14_P$14") (pintype "power_in"))
      (node (ref "7SEG15") (pin "P$14") (pinfunction "P$14_P$14") (pintype "power_in"))
      (node (ref "7SEG7") (pin "P$14") (pinfunction "P$14_P$14") (pintype "power_in"))
      (node (ref "R5") (pin "2") (pinfunction "2_2") (pintype "passive"))
    )
    (net (code "43") (name "/COM5") (class "Default")
      (node (ref "7SEG10") (pin "P$13") (pinfunction "P$13_P$13") (pintype "power_in"))
      (node (ref "7SEG12") (pin "P$13") (pinfunction "P$13_P$13") (pintype "power_in"))
      (node (ref "7SEG15") (pin "P$13") (pinfunction "P$13_P$13") (pintype "power_in"))
      (node (ref "7SEG7") (pin "P$13") (pinfunction "P$13_P$13") (pintype "power_in"))
      (node (ref "R6") (pin "2") (pinfunction "2_2") (pintype "passive"))
    )
    (net (code "44") (name "/COM6") (class "Default")
      (node (ref "7SEG11") (pin "P$14") (pinfunction "P$14_P$14") (pintype "power_in"))
      (node (ref "7SEG14") (pin "P$14") (pinfunction "P$14_P$14") (pintype "power_in"))
      (node (ref "7SEG16") (pin "P$14") (pinfunction "P$14_P$14") (pintype "power_in"))
      (node (ref "7SEG8") (pin "P$14") (pinfunction "P$14_P$14") (pintype "power_in"))
      (node (ref "R7") (pin "2") (pinfunction "2_2") (pintype "passive"))
    )
    (net (code "45") (name "/COM7") (class "Default")
      (node (ref "7SEG11") (pin "P$13") (pinfunction "P$13_P$13") (pintype "power_in"))
      (node (ref "7SEG14") (pin "P$13") (pinfunction "P$13_P$13") (pintype "power_in"))
      (node (ref "7SEG16") (pin "P$13") (pinfunction "P$13_P$13") (pintype "power_in"))
      (node (ref "7SEG8") (pin "P$13") (pinfunction "P$13_P$13") (pintype "power_in"))
      (node (ref "R8") (pin "2") (pinfunction "2_2") (pintype "passive"))
    )
    (net (code "46") (name "/CONF0") (class "Default")
      (node (ref "IC1") (pin "14") (pinfunction "SER_14") (pintype "input"))
      (node (ref "J1") (pin "1") (pinfunction "P1_1") (pintype "passive"))
      (node (ref "J2") (pin "1") (pinfunction "P1_1") (pintype "passive"))
      (node (ref "J3") (pin "1") (pinfunction "P1_1") (pintype "passive"))
    )
    (net (code "47") (name "/CONF1") (class "Default")
      (node (ref "IC1") (pin "11") (pinfunction "SCLK_11") (pintype "input"))
      (node (ref "IC2") (pin "11") (pinfunction "SCLK_11") (pintype "input"))
      (node (ref "IC3") (pin "11") (pinfunction "SCLK_11") (pintype "input"))
      (node (ref "IC4") (pin "11") (pinfunction "SCLK_11") (pintype "input"))
      (node (ref "IC5") (pin "11") (pinfunction "SCLK_11") (pintype "input"))
      (node (ref "J1") (pin "7") (pinfunction "P7_7") (pintype "passive"))
      (node (ref "J2") (pin "7") (pinfunction "P7_7") (pintype "passive"))
      (node (ref "J3") (pin "7") (pinfunction "P7_7") (pintype "passive"))
    )
    (net (code "48") (name "/CONF2") (class "Default")
      (node (ref "IC1") (pin "10") (pinfunction "~{SCLR}_10") (pintype "input"))
      (node (ref "IC2") (pin "10") (pinfunction "~{SCLR}_10") (pintype "input"))
      (node (ref "IC3") (pin "10") (pinfunction "~{SCLR}_10") (pintype "input"))
      (node (ref "IC4") (pin "10") (pinfunction "~{SCLR}_10") (pintype "input"))
      (node (ref "IC5") (pin "10") (pinfunction "~{SCLR}_10") (pintype "input"))
      (node (ref "J1") (pin "9") (pinfunction "P9_9") (pintype "passive"))
      (node (ref "J2") (pin "9") (pinfunction "P9_9") (pintype "passive"))
      (node (ref "J3") (pin "9") (pinfunction "P9_9") (pintype "passive"))
    )
    (net (code "49") (name "/CONF3") (class "Default")
      (node (ref "IC1") (pin "12") (pinfunction "RCLK_12") (pintype "input"))
      (node (ref "IC2") (pin "12") (pinfunction "RCLK_12") (pintype "input"))
      (node (ref "IC3") (pin "12") (pinfunction "RCLK_12") (pintype "input"))
      (node (ref "IC4") (pin "12") (pinfunction "RCLK_12") (pintype "input"))
      (node (ref "IC5") (pin "12") (pinfunction "RCLK_12") (pintype "input"))
      (node (ref "J1") (pin "5") (pinfunction "P5_5") (pintype "passive"))
      (node (ref "J2") (pin "5") (pinfunction "P5_5") (pintype "passive"))
      (node (ref "J3") (pin "5") (pinfunction "P5_5") (pintype "passive"))
    )
    (net (code "50") (name "/CONF4") (class "Default")
      (node (ref "IC1") (pin "13") (pinfunction "~{OE}_13") (pintype "input"))
      (node (ref "IC2") (pin "13") (pinfunction "~{OE}_13") (pintype "input"))
      (node (ref "IC3") (pin "13") (pinfunction "~{OE}_13") (pintype "input"))
      (node (ref "IC4") (pin "13") (pinfunction "~{OE}_13") (pintype "input"))
      (node (ref "IC5") (pin "13") (pinfunction "~{OE}_13") (pintype "input"))
      (node (ref "J1") (pin "3") (pinfunction "P3_3") (pintype "passive"))
      (node (ref "J2") (pin "3") (pinfunction "P3_3") (pintype "passive"))
      (node (ref "J3") (pin "3") (pinfunction "P3_3") (pintype "passive"))
    )
    (net (code "51") (name "/CONF5") (class "Default")
      (node (ref "IC4") (pin "9") (pinfunction "QH'_9") (pintype "tri_state"))
      (node (ref "J1") (pin "10") (pinfunction "P10_10") (pintype "passive"))
      (node (ref "J2") (pin "10") (pinfunction "P10_10") (pintype "passive"))
      (node (ref "J3") (pin "10") (pinfunction "P10_10") (pintype "passive"))
    )
    (net (code "52") (name "/CONF6") (class "Default")
      (node (ref "IC5") (pin "14") (pinfunction "SER_14") (pintype "input"))
      (node (ref "J1") (pin "8") (pinfunction "P8_8") (pintype "passive"))
      (node (ref "J2") (pin "8") (pinfunction "P8_8") (pintype "passive"))
      (node (ref "J3") (pin "8") (pinfunction "P8_8") (pintype "passive"))
    )
    (net (code "54") (name "GND") (class "Default")
      (node (ref "C1") (pin "2") (pinfunction "2_2") (pintype "passive"))
      (node (ref "C2") (pin "2") (pinfunction "2_2") (pintype "passive"))
      (node (ref "C3") (pin "2") (pinfunction "2_2") (pintype "passive"))
      (node (ref "C4") (pin "2") (pinfunction "2_2") (pintype "passive"))
      (node (ref "C5") (pin "2") (pinfunction "2_2") (pintype "passive"))
      (node (ref "IC1") (pin "8") (pinfunction "GND_8") (pintype "power_in"))
      (node (ref "IC2") (pin "8") (pinfunction "GND_8") (pintype "power_in"))
      (node (ref "IC3") (pin "8") (pinfunction "GND_8") (pintype "power_in"))
      (node (ref "IC4") (pin "8") (pinfunction "GND_8") (pintype "power_in"))
      (node (ref "IC5") (pin "8") (pinfunction "GND_8") (pintype "power_in"))
      (node (ref "J1") (pin "6") (pinfunction "P6_6") (pintype "passive"))
      (node (ref "J2") (pin "6") (pinfunction "P6_6") (pintype "passive"))
      (node (ref "J3") (pin "6") (pinfunction "P6_6") (pintype "passive"))
      (node (ref "Q1") (pin "9") (pinfunction "GND_9") (pintype "bidirectional"))
    )
    (net (code "55") (name "Net-(IC1-QH')") (class "Default")
      (node (ref "IC1") (pin "9") (pinfunction "QH'_9") (pintype "tri_state"))
      (node (ref "IC2") (pin "14") (pinfunction "SER_14") (pintype "input"))
    )
    (net (code "56") (name "Net-(IC2-QH')") (class "Default")
      (node (ref "IC2") (pin "9") (pinfunction "QH'_9") (pintype "tri_state"))
      (node (ref "IC3") (pin "14") (pinfunction "SER_14") (pintype "input"))
    )
    (net (code "57") (name "Net-(IC3-QH')") (class "Default")
      (node (ref "IC3") (pin "9") (pinfunction "QH'_9") (pintype "tri_state"))
      (node (ref "IC4") (pin "14") (pinfunction "SER_14") (pintype "input"))
    )
    (net (code "58") (name "Net-(IC5-QA)") (class "Default")
      (node (ref "IC5") (pin "15") (pinfunction "QA_15") (pintype "tri_state"))
      (node (ref "Q1") (pin "8") (pinfunction "I8_8") (pintype "bidirectional"))
    )
    (net (code "59") (name "Net-(IC5-QB)") (class "Default")
      (node (ref "IC5") (pin "1") (pinfunction "QB_1") (pintype "tri_state"))
      (node (ref "Q1") (pin "7") (pinfunction "I7_7") (pintype "bidirectional"))
    )
    (net (code "60") (name "Net-(IC5-QC)") (class "Default")
      (node (ref "IC5") (pin "2") (pinfunction "QC_2") (pintype "tri_state"))
      (node (ref "Q1") (pin "6") (pinfunction "I6_6") (pintype "bidirectional"))
    )
    (net (code "61") (name "Net-(IC5-QD)") (class "Default")
      (node (ref "IC5") (pin "3") (pinfunction "QD_3") (pintype "tri_state"))
      (node (ref "Q1") (pin "5") (pinfunction "I5_5") (pintype "bidirectional"))
    )
    (net (code "62") (name "Net-(IC5-QE)") (class "Default")
      (node (ref "IC5") (pin "4") (pinfunction "QE_4") (pintype "tri_state"))
      (node (ref "Q1") (pin "4") (pinfunction "I4_4") (pintype "bidirectional"))
    )
    (net (code "63") (name "Net-(IC5-QF)") (class "Default")
      (node (ref "IC5") (pin "5") (pinfunction "QF_5") (pintype "tri_state"))
      (node (ref "Q1") (pin "3") (pinfunction "I3_3") (pintype "bidirectional"))
    )
    (net (code "64") (name "Net-(IC5-QG)") (class "Default")
      (node (ref "IC5") (pin "6") (pinfunction "QG_6") (pintype "tri_state"))
      (node (ref "Q1") (pin "2") (pinfunction "I2_2") (pintype "bidirectional"))
    )
    (net (code "65") (name "Net-(IC5-QH)") (class "Default")
      (node (ref "IC5") (pin "7") (pinfunction "QH_7") (pintype "tri_state"))
      (node (ref "Q1") (pin "1") (pinfunction "I1_1") (pintype "bidirectional"))
    )
    (net (code "66") (name "Net-(Q1-O1)") (class "Default")
      (node (ref "Q1") (pin "18") (pinfunction "O1_18") (pintype "bidirectional"))
      (node (ref "R1") (pin "1") (pinfunction "1_1") (pintype "passive"))
    )
    (net (code "67") (name "Net-(Q1-O2)") (class "Default")
      (node (ref "Q1") (pin "17") (pinfunction "O2_17") (pintype "bidirectional"))
      (node (ref "R2") (pin "1") (pinfunction "1_1") (pintype "passive"))
    )
    (net (code "68") (name "Net-(Q1-O3)") (class "Default")
      (node (ref "Q1") (pin "16") (pinfunction "O3_16") (pintype "bidirectional"))
      (node (ref "R3") (pin "1") (pinfunction "1_1") (pintype "passive"))
    )
    (net (code "69") (name "Net-(Q1-O4)") (class "Default")
      (node (ref "Q1") (pin "15") (pinfunction "O4_15") (pintype "bidirectional"))
      (node (ref "R4") (pin "1") (pinfunction "1_1") (pintype "passive"))
    )
    (net (code "70") (name "Net-(Q1-O5)") (class "Default")
      (node (ref "Q1") (pin "14") (pinfunction "O5_14") (pintype "bidirectional"))
      (node (ref "R5") (pin "1") (pinfunction "1_1") (pintype "passive"))
    )
    (net (code "71") (name "Net-(Q1-O6)") (class "Default")
      (node (ref "Q1") (pin "13") (pinfunction "O6_13") (pintype "bidirectional"))
      (node (ref "R6") (pin "1") (pinfunction "1_1") (pintype "passive"))
    )
    (net (code "72") (name "Net-(Q1-O7)") (class "Default")
      (node (ref "Q1") (pin "12") (pinfunction "O7_12") (pintype "bidirectional"))
      (node (ref "R7") (pin "1") (pinfunction "1_1") (pintype "passive"))
    )
    (net (code "73") (name "Net-(Q1-O8)") (class "Default")
      (node (ref "Q1") (pin "11") (pinfunction "O8_11") (pintype "bidirectional"))
      (node (ref "R8") (pin "1") (pinfunction "1_1") (pintype "passive"))
    )
    (net (code "74") (name "VCC") (class "Default")
      (node (ref "C1") (pin "1") (pinfunction "1_1") (pintype "passive"))
      (node (ref "C2") (pin "1") (pinfunction "1_1") (pintype "passive"))
      (node (ref "C3") (pin "1") (pinfunction "1_1") (pintype "passive"))
      (node (ref "C4") (pin "1") (pinfunction "1_1") (pintype "passive"))
      (node (ref "C5") (pin "1") (pinfunction "1_1") (pintype "passive"))
      (node (ref "IC1") (pin "16") (pinfunction "VCC_16") (pintype "power_in"))
      (node (ref "IC2") (pin "16") (pinfunction "VCC_16") (pintype "power_in"))
      (node (ref "IC3") (pin "16") (pinfunction "VCC_16") (pintype "power_in"))
      (node (ref "IC4") (pin "16") (pinfunction "VCC_16") (pintype "power_in"))
      (node (ref "IC5") (pin "16") (pinfunction "VCC_16") (pintype "power_in"))
      (node (ref "J1") (pin "4") (pinfunction "P4_4") (pintype "passive"))
      (node (ref "J2") (pin "4") (pinfunction "P4_4") (pintype "passive"))
      (node (ref "J3") (pin "4") (pinfunction "P4_4") (pintype "passive"))
    )
    (net (code "75") (name "unconnected-(IC5-QH'-Pad9)") (class "Default")
      (node (ref "IC5") (pin "9") (pinfunction "QH'_9") (pintype "tri_state"))
    )
    (net (code "76") (name "unconnected-(J1-P2-Pad2)") (class "Default")
      (node (ref "J1") (pin "2") (pinfunction "P2_2") (pintype "passive"))
    )
    (net (code "77") (name "unconnected-(J2-P2-Pad2)") (class "Default")
      (node (ref "J2") (pin "2") (pinfunction "P2_2") (pintype "passive"))
    )
    (net (code "78") (name "unconnected-(J3-P2-Pad2)") (class "Default")
      (node (ref "J3") (pin "2") (pinfunction "P2_2") (pintype "passive"))
    )
    (net (code "79") (name "unconnected-(Q1-COMMON-Pad10)") (class "Default")
      (node (ref "Q1") (pin "10") (pinfunction "COMMON_10") (pintype "bidirectional"))
    )
  )
)
